# LedController.net
KiCad netlist of a schematic drawn in EAGLE
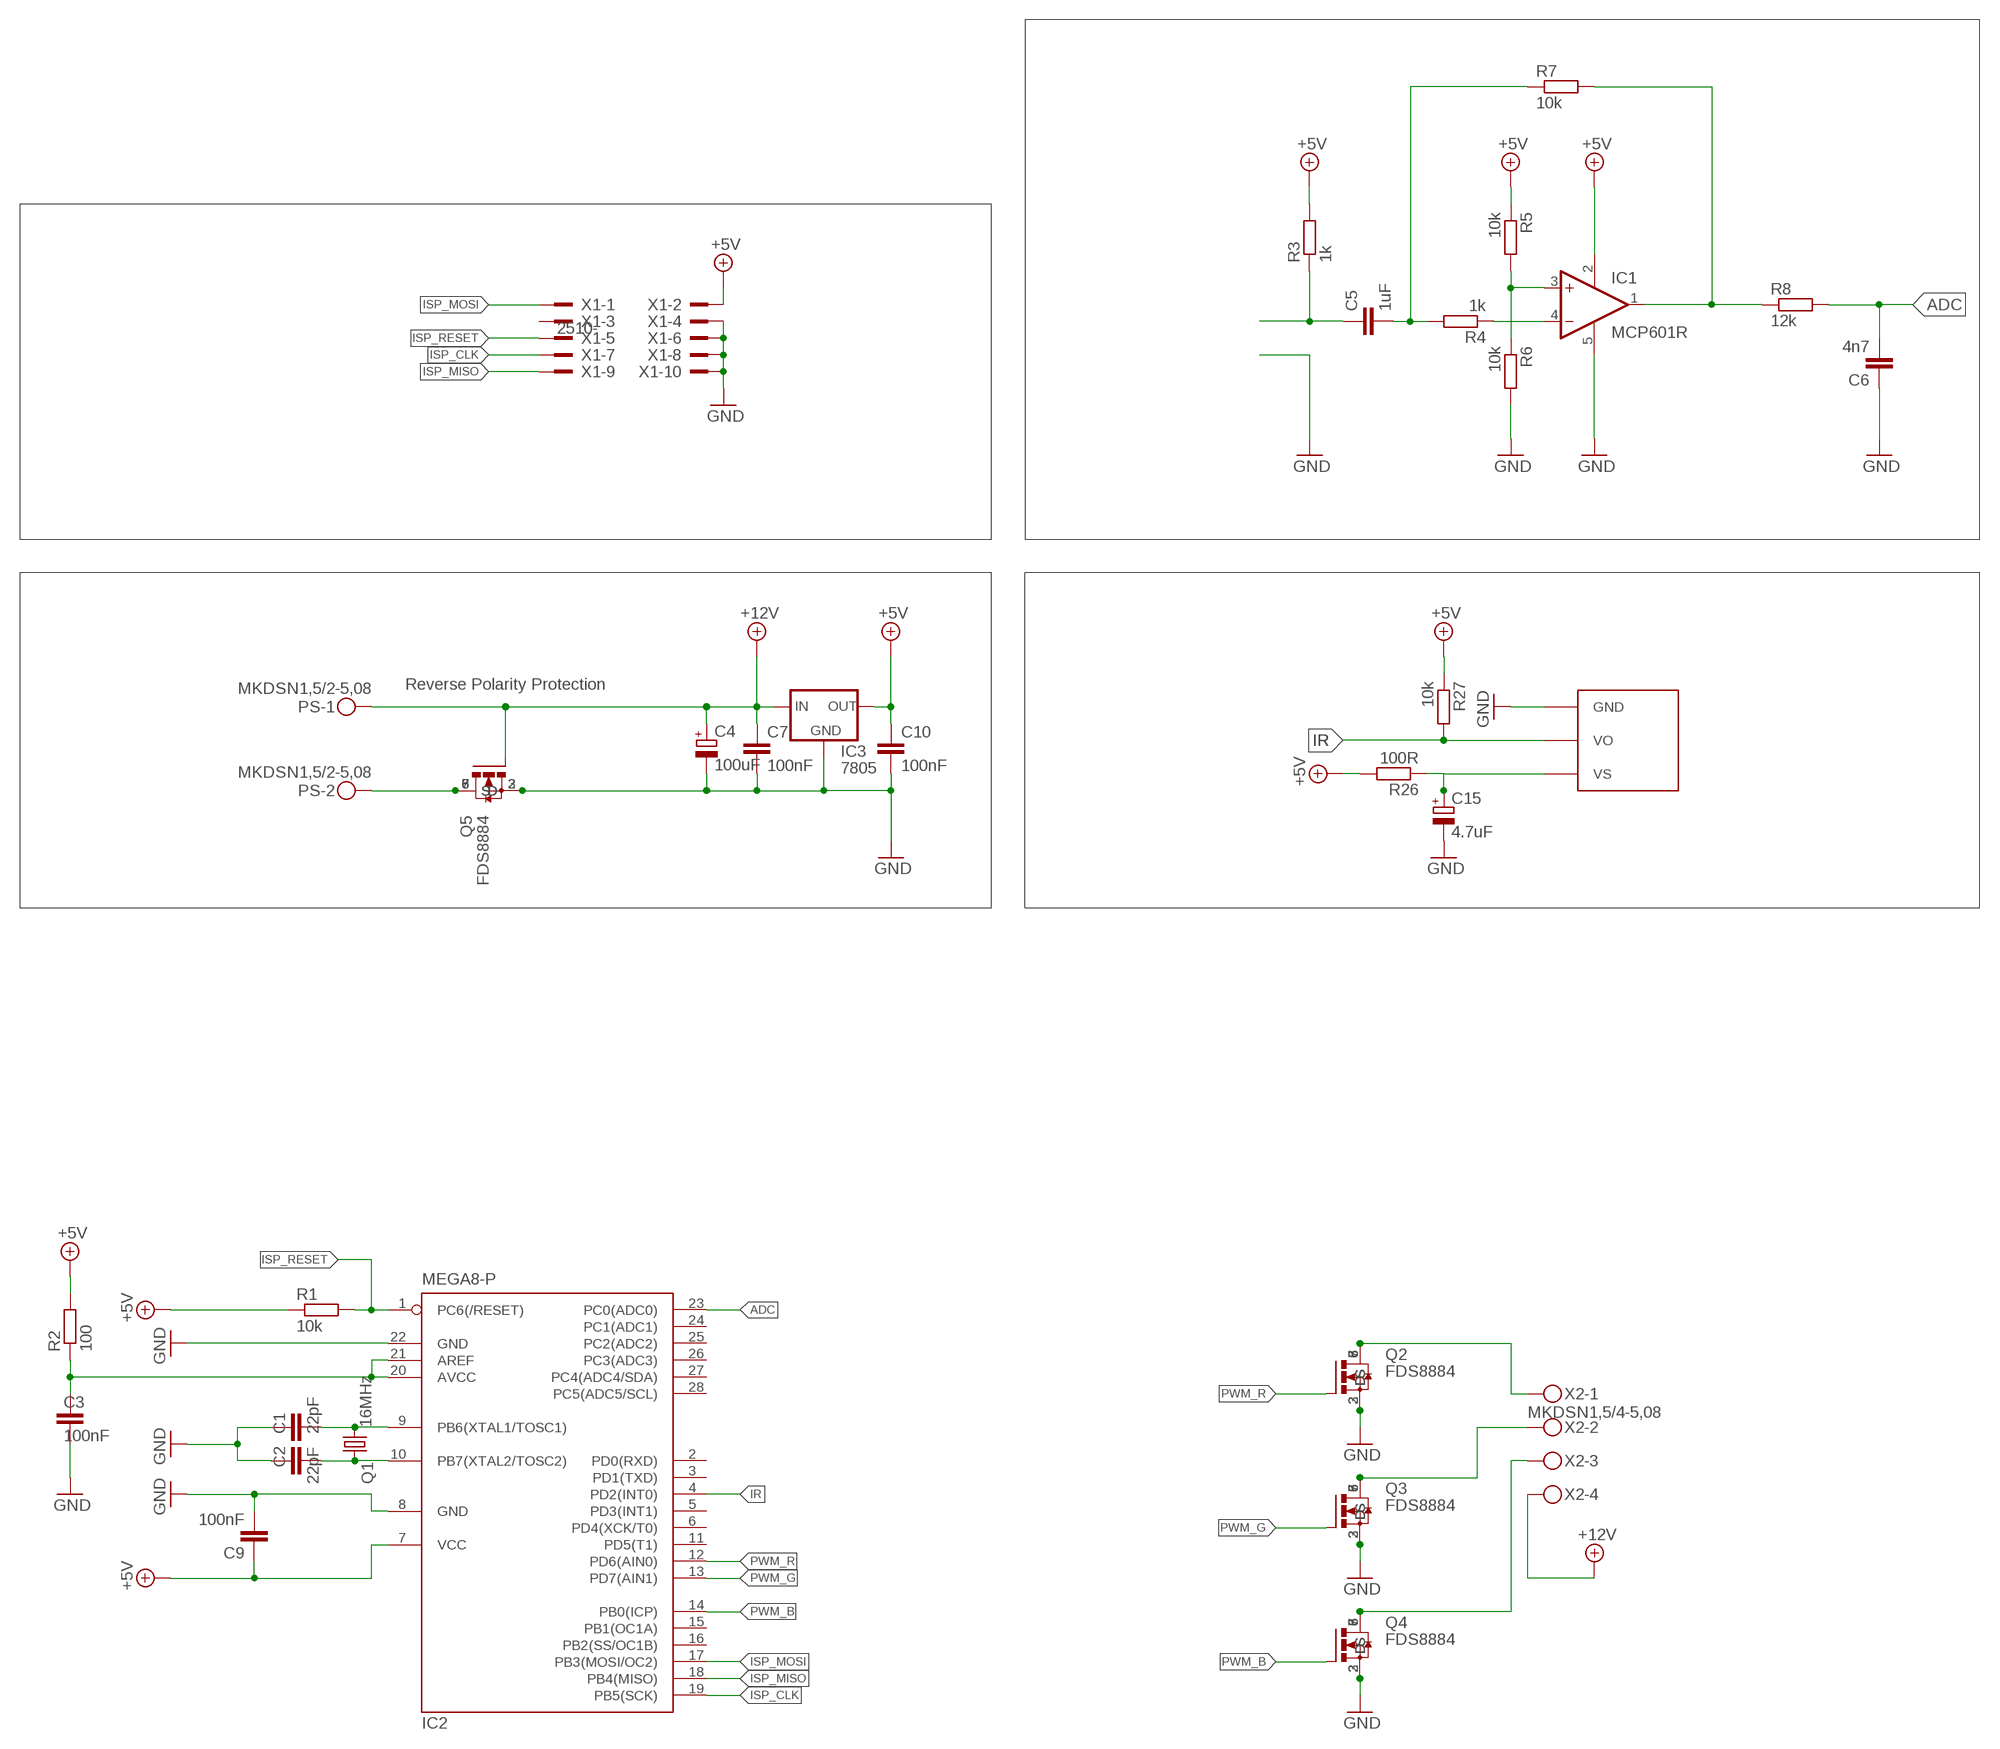
[diagram p0: schematic, sheet 1]

(export (version "E")
  (design (tool "Eeschema 10.0.6"))
  (components
    (comp (ref "C1")
      (value "22pF")
      (footprint "eagle-import:C025-025X050")
      (libsource (lib "eagle-import") (part "C-EU025-025X050"))
    )
    (comp (ref "C2")
      (value "22pF")
      (footprint "eagle-import:C025-025X050")
      (libsource (lib "eagle-import") (part "C-EU025-025X050"))
    )
    (comp (ref "C3")
      (value "100nF")
      (footprint "eagle-import:C025-025X050")
      (libsource (lib "eagle-import") (part "C-EU025-025X050"))
    )
    (comp (ref "C4")
      (value "100uF")
      (footprint "eagle-import:E2-5")
      (libsource (lib "eagle-import") (part "CPOL-EUE2-5"))
    )
    (comp (ref "C5")
      (value "1uF")
      (footprint "eagle-import:C025-024X044")
      (libsource (lib "eagle-import") (part "C-EU025-024X044"))
    )
    (comp (ref "C6")
      (value "4n7")
      (footprint "eagle-import:C025-024X044")
      (libsource (lib "eagle-import") (part "C-EU025-024X044"))
    )
    (comp (ref "C7")
      (value "100nF")
      (footprint "eagle-import:C025-024X044")
      (libsource (lib "eagle-import") (part "C-EU025-024X044"))
    )
    (comp (ref "C9")
      (value "100nF")
      (footprint "eagle-import:C025-024X044")
      (libsource (lib "eagle-import") (part "C-EU025-024X044"))
    )
    (comp (ref "C10")
      (value "100nF")
      (footprint "eagle-import:C025-024X044")
      (libsource (lib "eagle-import") (part "C-EU025-024X044"))
    )
    (comp (ref "C15")
      (value "4.7uF")
      (footprint "eagle-import:E2-5")
      (libsource (lib "eagle-import") (part "CPOL-EUE2-5"))
    )
    (comp (ref "IC1")
      (value "MCP601R")
      (footprint "eagle-import:SOT23-5")
      (libsource (lib "eagle-import") (part "MCP601R"))
    )
    (comp (ref "IC2")
      (value "MEGA8-P")
      (footprint "eagle-import:DIL28-3")
      (libsource (lib "eagle-import") (part "MEGA8-P"))
    )
    (comp (ref "IC3")
      (value "7805")
      (footprint "eagle-import:78XXS")
      (libsource (lib "eagle-import") (part "78XXS"))
    )
    (comp (ref "PS")
      (value "MKDSN1,5/2-5,08")
      (footprint "eagle-import:MKDSN1,5_2-5,08")
      (libsource (lib "eagle-import") (part "MKDSN1,5/2-5,08"))
    )
    (comp (ref "Q1")
      (value "16MHz")
      (footprint "eagle-import:HC49_S")
      (libsource (lib "eagle-import") (part "CRYSTALHC49S"))
    )
    (comp (ref "Q2")
      (value "FDS8884")
      (footprint "eagle-import:SO08")
      (libsource (lib "eagle-import") (part "FDS8884"))
    )
    (comp (ref "Q3")
      (value "FDS8884")
      (footprint "eagle-import:SO08")
      (libsource (lib "eagle-import") (part "FDS8884"))
    )
    (comp (ref "Q4")
      (value "FDS8884")
      (footprint "eagle-import:SO08")
      (libsource (lib "eagle-import") (part "FDS8884"))
    )
    (comp (ref "Q5")
      (value "FDS8884")
      (footprint "eagle-import:SO08")
      (libsource (lib "eagle-import") (part "FDS8884"))
    )
    (comp (ref "R1")
      (value "10k")
      (footprint "eagle-import:0207_2V")
      (libsource (lib "eagle-import") (part "R-EU_0207/2V"))
    )
    (comp (ref "R2")
      (value "100")
      (footprint "eagle-import:0207_2V")
      (libsource (lib "eagle-import") (part "R-EU_0207/2V"))
    )
    (comp (ref "R3")
      (value "1k")
      (footprint "eagle-import:0207_2V")
      (libsource (lib "eagle-import") (part "R-EU_0207/2V"))
    )
    (comp (ref "R4")
      (value "1k")
      (footprint "eagle-import:0207_2V")
      (libsource (lib "eagle-import") (part "R-EU_0207/2V"))
    )
    (comp (ref "R5")
      (value "10k")
      (footprint "eagle-import:0207_2V")
      (libsource (lib "eagle-import") (part "R-EU_0207/2V"))
    )
    (comp (ref "R6")
      (value "10k")
      (footprint "eagle-import:0207_2V")
      (libsource (lib "eagle-import") (part "R-EU_0207/2V"))
    )
    (comp (ref "R7")
      (value "10k")
      (footprint "eagle-import:0207_2V")
      (libsource (lib "eagle-import") (part "R-EU_0207/2V"))
    )
    (comp (ref "R8")
      (value "12k")
      (footprint "eagle-import:0207_2V")
      (libsource (lib "eagle-import") (part "R-EU_0207/2V"))
    )
    (comp (ref "R26")
      (value "100R")
      (footprint "eagle-import:0207_10")
      (libsource (lib "eagle-import") (part "R-EU_0207/10"))
    )
    (comp (ref "R27")
      (value "10k")
      (footprint "eagle-import:0207_10")
      (libsource (lib "eagle-import") (part "R-EU_0207/10"))
    )
    (comp (ref "TSOP")
      (value "TSOP")
      (footprint "eagle-import:TSOP")
      (libsource (lib "eagle-import") (part "TSOP"))
    )
    (comp (ref "X1")
      (value "2510-")
      (footprint "eagle-import:PAK100_2500-10")
      (libsource (lib "eagle-import") (part "2510-"))
    )
    (comp (ref "X2")
      (value "MKDSN1,5/4-5,08")
      (footprint "eagle-import:MKDSN1,5_4-5,08")
      (libsource (lib "eagle-import") (part "MKDSN1,5/4-5,08"))
    )
  )
  (nets
    (net (code "1") (name "+5V") (class "Default")
      (node (ref "C10") (pin "1") (pinfunction "1_1") (pintype "passive"))
      (node (ref "C9") (pin "1") (pinfunction "1_1") (pintype "passive"))
      (node (ref "IC1") (pin "2") (pinfunction "V+_2") (pintype "power_in"))
      (node (ref "IC2") (pin "7") (pinfunction "VCC_7") (pintype "power_in"))
      (node (ref "IC3") (pin "OUT") (pinfunction "OUT_OUT") (pintype "passive"))
      (node (ref "R1") (pin "1") (pinfunction "1_1") (pintype "passive"))
      (node (ref "R2") (pin "2") (pinfunction "2_2") (pintype "passive"))
      (node (ref "R26") (pin "2") (pinfunction "2_2") (pintype "passive"))
      (node (ref "R27") (pin "1") (pinfunction "1_1") (pintype "passive"))
      (node (ref "R3") (pin "2") (pinfunction "2_2") (pintype "passive"))
      (node (ref "R5") (pin "1") (pinfunction "1_1") (pintype "passive"))
      (node (ref "X1") (pin "2") (pinfunction "KL_2") (pintype "passive"))
    )
    (net (code "2") (name "+12V") (class "Default")
      (node (ref "C4") (pin "+") (pinfunction "+_+") (pintype "passive"))
      (node (ref "C7") (pin "1") (pinfunction "1_1") (pintype "passive"))
      (node (ref "IC3") (pin "IN") (pinfunction "IN_IN") (pintype "input"))
      (node (ref "PS") (pin "1") (pinfunction "KL_1") (pintype "passive"))
      (node (ref "Q5") (pin "4") (pinfunction "G_4") (pintype "passive"))
      (node (ref "X2") (pin "4") (pinfunction "KL_4") (pintype "passive"))
    )
    (net (code "3") (name "ADC") (class "Default")
      (node (ref "C6") (pin "2") (pinfunction "2_2") (pintype "passive"))
      (node (ref "IC2") (pin "23") (pinfunction "PC0(ADC0)_23") (pintype "bidirectional"))
      (node (ref "R8") (pin "2") (pinfunction "2_2") (pintype "passive"))
    )
    (net (code "4") (name "GND") (class "Default")
      (node (ref "C1") (pin "1") (pinfunction "1_1") (pintype "passive"))
      (node (ref "C10") (pin "2") (pinfunction "2_2") (pintype "passive"))
      (node (ref "C15") (pin "-") (pinfunction "-_-") (pintype "passive"))
      (node (ref "C2") (pin "1") (pinfunction "1_1") (pintype "passive"))
      (node (ref "C3") (pin "2") (pinfunction "2_2") (pintype "passive"))
      (node (ref "C4") (pin "-") (pinfunction "-_-") (pintype "passive"))
      (node (ref "C6") (pin "1") (pinfunction "1_1") (pintype "passive"))
      (node (ref "C7") (pin "2") (pinfunction "2_2") (pintype "passive"))
      (node (ref "C9") (pin "2") (pinfunction "2_2") (pintype "passive"))
      (node (ref "IC1") (pin "5") (pinfunction "V-_5") (pintype "power_in"))
      (node (ref "IC2") (pin "22") (pinfunction "GND_22") (pintype "power_in"))
      (node (ref "IC2") (pin "8") (pinfunction "GND_8") (pintype "power_in"))
      (node (ref "IC3") (pin "GND") (pinfunction "GND_GND") (pintype "input"))
      (node (ref "Q2") (pin "1") (pinfunction "S_1") (pintype "passive"))
      (node (ref "Q2") (pin "2") (pinfunction "S_2") (pintype "bidirectional"))
      (node (ref "Q2") (pin "3") (pinfunction "S_3") (pintype "bidirectional"))
      (node (ref "Q3") (pin "1") (pinfunction "S_1") (pintype "passive"))
      (node (ref "Q3") (pin "2") (pinfunction "S_2") (pintype "bidirectional"))
      (node (ref "Q3") (pin "3") (pinfunction "S_3") (pintype "bidirectional"))
      (node (ref "Q4") (pin "1") (pinfunction "S_1") (pintype "passive"))
      (node (ref "Q4") (pin "2") (pinfunction "S_2") (pintype "bidirectional"))
      (node (ref "Q4") (pin "3") (pinfunction "S_3") (pintype "bidirectional"))
      (node (ref "Q5") (pin "1") (pinfunction "S_1") (pintype "passive"))
      (node (ref "Q5") (pin "2") (pinfunction "S_2") (pintype "bidirectional"))
      (node (ref "Q5") (pin "3") (pinfunction "S_3") (pintype "bidirectional"))
      (node (ref "R6") (pin "2") (pinfunction "2_2") (pintype "passive"))
      (node (ref "TSOP") (pin "GND") (pinfunction "GND_GND") (pintype "bidirectional"))
      (node (ref "X1") (pin "10") (pinfunction "KL_10") (pintype "passive"))
      (node (ref "X1") (pin "4") (pinfunction "KL_4") (pintype "passive"))
      (node (ref "X1") (pin "6") (pinfunction "KL_6") (pintype "passive"))
      (node (ref "X1") (pin "8") (pinfunction "KL_8") (pintype "passive"))
    )
    (net (code "5") (name "IR") (class "Default")
      (node (ref "IC2") (pin "4") (pinfunction "PD2(INT0)_4") (pintype "bidirectional"))
      (node (ref "R27") (pin "2") (pinfunction "2_2") (pintype "passive"))
      (node (ref "TSOP") (pin "VO") (pinfunction "VO_VO") (pintype "bidirectional"))
    )
    (net (code "6") (name "ISP_CLK") (class "Default")
      (node (ref "IC2") (pin "19") (pinfunction "PB5(SCK)_19") (pintype "bidirectional"))
      (node (ref "X1") (pin "7") (pinfunction "KL_7") (pintype "passive"))
    )
    (net (code "7") (name "ISP_MISO") (class "Default")
      (node (ref "IC2") (pin "18") (pinfunction "PB4(MISO)_18") (pintype "bidirectional"))
      (node (ref "X1") (pin "9") (pinfunction "KL_9") (pintype "passive"))
    )
    (net (code "8") (name "ISP_MOSI") (class "Default")
      (node (ref "IC2") (pin "17") (pinfunction "PB3(MOSI/OC2)_17") (pintype "bidirectional"))
      (node (ref "X1") (pin "1") (pinfunction "KL_1") (pintype "passive"))
    )
    (net (code "9") (name "ISP_RESET") (class "Default")
      (node (ref "IC2") (pin "1") (pinfunction "PC6(/RESET)_1") (pintype "bidirectional"))
      (node (ref "R1") (pin "2") (pinfunction "2_2") (pintype "passive"))
      (node (ref "X1") (pin "5") (pinfunction "KL_5") (pintype "passive"))
    )
    (net (code "10") (name "Net-(C5-Pad1)") (class "Default")
      (node (ref "C5") (pin "1") (pinfunction "1_1") (pintype "passive"))
      (node (ref "R3") (pin "1") (pinfunction "1_1") (pintype "passive"))
    )
    (net (code "11") (name "Net-(C5-Pad2)") (class "Default")
      (node (ref "C5") (pin "2") (pinfunction "2_2") (pintype "passive"))
      (node (ref "R4") (pin "2") (pinfunction "2_2") (pintype "passive"))
      (node (ref "R7") (pin "1") (pinfunction "1_1") (pintype "passive"))
    )
    (net (code "12") (name "Net-(C15-Pad+)") (class "Default")
      (node (ref "C15") (pin "+") (pinfunction "+_+") (pintype "passive"))
      (node (ref "R26") (pin "1") (pinfunction "1_1") (pintype "passive"))
      (node (ref "TSOP") (pin "VS") (pinfunction "VS_VS") (pintype "bidirectional"))
    )
    (net (code "13") (name "Net-(IC1-+IN)") (class "Default")
      (node (ref "IC1") (pin "3") (pinfunction "+IN_3") (pintype "input"))
      (node (ref "R5") (pin "2") (pinfunction "2_2") (pintype "passive"))
      (node (ref "R6") (pin "1") (pinfunction "1_1") (pintype "passive"))
    )
    (net (code "14") (name "Net-(IC1--IN)") (class "Default")
      (node (ref "IC1") (pin "4") (pinfunction "-IN_4") (pintype "input"))
      (node (ref "R4") (pin "1") (pinfunction "1_1") (pintype "passive"))
    )
    (net (code "15") (name "Net-(IC1-OUT)") (class "Default")
      (node (ref "IC1") (pin "1") (pinfunction "OUT_1") (pintype "output"))
      (node (ref "R7") (pin "2") (pinfunction "2_2") (pintype "passive"))
      (node (ref "R8") (pin "1") (pinfunction "1_1") (pintype "passive"))
    )
    (net (code "16") (name "Net-(IC2-AREF)") (class "Default")
      (node (ref "C3") (pin "1") (pinfunction "1_1") (pintype "passive"))
      (node (ref "IC2") (pin "20") (pinfunction "AVCC_20") (pintype "power_in"))
      (node (ref "IC2") (pin "21") (pinfunction "AREF_21") (pintype "passive"))
      (node (ref "R2") (pin "1") (pinfunction "1_1") (pintype "passive"))
    )
    (net (code "17") (name "Net-(IC2-PB6(XTAL1{slash}TOSC1))") (class "Default")
      (node (ref "C1") (pin "2") (pinfunction "2_2") (pintype "passive"))
      (node (ref "IC2") (pin "9") (pinfunction "PB6(XTAL1/TOSC1)_9") (pintype "bidirectional"))
      (node (ref "Q1") (pin "2") (pinfunction "2_2") (pintype "passive"))
    )
    (net (code "18") (name "Net-(IC2-PB7(XTAL2{slash}TOSC2))") (class "Default")
      (node (ref "C2") (pin "2") (pinfunction "2_2") (pintype "passive"))
      (node (ref "IC2") (pin "10") (pinfunction "PB7(XTAL2/TOSC2)_10") (pintype "bidirectional"))
      (node (ref "Q1") (pin "1") (pinfunction "1_1") (pintype "passive"))
    )
    (net (code "19") (name "Net-(PSB-KL)") (class "Default")
      (node (ref "PS") (pin "2") (pinfunction "KL_2") (pintype "passive"))
      (node (ref "Q5") (pin "5") (pinfunction "D_5") (pintype "passive"))
      (node (ref "Q5") (pin "6") (pinfunction "D_6") (pintype "bidirectional"))
      (node (ref "Q5") (pin "7") (pinfunction "D_7") (pintype "bidirectional"))
      (node (ref "Q5") (pin "8") (pinfunction "D_8") (pintype "bidirectional"))
    )
    (net (code "20") (name "Net-(X2A-KL)") (class "Default")
      (node (ref "Q2") (pin "5") (pinfunction "D_5") (pintype "passive"))
      (node (ref "Q2") (pin "6") (pinfunction "D_6") (pintype "bidirectional"))
      (node (ref "Q2") (pin "7") (pinfunction "D_7") (pintype "bidirectional"))
      (node (ref "Q2") (pin "8") (pinfunction "D_8") (pintype "bidirectional"))
      (node (ref "X2") (pin "1") (pinfunction "KL_1") (pintype "passive"))
    )
    (net (code "21") (name "Net-(X2B-KL)") (class "Default")
      (node (ref "Q3") (pin "5") (pinfunction "D_5") (pintype "passive"))
      (node (ref "Q3") (pin "6") (pinfunction "D_6") (pintype "bidirectional"))
      (node (ref "Q3") (pin "7") (pinfunction "D_7") (pintype "bidirectional"))
      (node (ref "Q3") (pin "8") (pinfunction "D_8") (pintype "bidirectional"))
      (node (ref "X2") (pin "2") (pinfunction "KL_2") (pintype "passive"))
    )
    (net (code "22") (name "Net-(X2C-KL)") (class "Default")
      (node (ref "Q4") (pin "5") (pinfunction "D_5") (pintype "passive"))
      (node (ref "Q4") (pin "6") (pinfunction "D_6") (pintype "bidirectional"))
      (node (ref "Q4") (pin "7") (pinfunction "D_7") (pintype "bidirectional"))
      (node (ref "Q4") (pin "8") (pinfunction "D_8") (pintype "bidirectional"))
      (node (ref "X2") (pin "3") (pinfunction "KL_3") (pintype "passive"))
    )
    (net (code "23") (name "PWM_B") (class "Default")
      (node (ref "IC2") (pin "14") (pinfunction "PB0(ICP)_14") (pintype "bidirectional"))
      (node (ref "Q4") (pin "4") (pinfunction "G_4") (pintype "passive"))
    )
    (net (code "24") (name "PWM_G") (class "Default")
      (node (ref "IC2") (pin "13") (pinfunction "PD7(AIN1)_13") (pintype "bidirectional"))
      (node (ref "Q3") (pin "4") (pinfunction "G_4") (pintype "passive"))
    )
    (net (code "25") (name "PWM_R") (class "Default")
      (node (ref "IC2") (pin "12") (pinfunction "PD6(AIN0)_12") (pintype "bidirectional"))
      (node (ref "Q2") (pin "4") (pinfunction "G_4") (pintype "passive"))
    )
    (net (code "26") (name "unconnected-(IC2-PB1(OC1A)-Pad15)") (class "Default")
      (node (ref "IC2") (pin "15") (pinfunction "PB1(OC1A)_15") (pintype "bidirectional"))
    )
    (net (code "27") (name "unconnected-(IC2-PB2(SS{slash}OC1B)-Pad16)") (class "Default")
      (node (ref "IC2") (pin "16") (pinfunction "PB2(SS/OC1B)_16") (pintype "bidirectional"))
    )
    (net (code "28") (name "unconnected-(IC2-PC1(ADC1)-Pad24)") (class "Default")
      (node (ref "IC2") (pin "24") (pinfunction "PC1(ADC1)_24") (pintype "bidirectional"))
    )
    (net (code "29") (name "unconnected-(IC2-PC2(ADC2)-Pad25)") (class "Default")
      (node (ref "IC2") (pin "25") (pinfunction "PC2(ADC2)_25") (pintype "bidirectional"))
    )
    (net (code "30") (name "unconnected-(IC2-PC3(ADC3)-Pad26)") (class "Default")
      (node (ref "IC2") (pin "26") (pinfunction "PC3(ADC3)_26") (pintype "bidirectional"))
    )
    (net (code "31") (name "unconnected-(IC2-PC4(ADC4{slash}SDA)-Pad27)") (class "Default")
      (node (ref "IC2") (pin "27") (pinfunction "PC4(ADC4/SDA)_27") (pintype "bidirectional"))
    )
    (net (code "32") (name "unconnected-(IC2-PC5(ADC5{slash}SCL)-Pad28)") (class "Default")
      (node (ref "IC2") (pin "28") (pinfunction "PC5(ADC5/SCL)_28") (pintype "bidirectional"))
    )
    (net (code "33") (name "unconnected-(IC2-PD0(RXD)-Pad2)") (class "Default")
      (node (ref "IC2") (pin "2") (pinfunction "PD0(RXD)_2") (pintype "bidirectional"))
    )
    (net (code "34") (name "unconnected-(IC2-PD1(TXD)-Pad3)") (class "Default")
      (node (ref "IC2") (pin "3") (pinfunction "PD1(TXD)_3") (pintype "bidirectional"))
    )
    (net (code "35") (name "unconnected-(IC2-PD3(INT1)-Pad5)") (class "Default")
      (node (ref "IC2") (pin "5") (pinfunction "PD3(INT1)_5") (pintype "bidirectional"))
    )
    (net (code "36") (name "unconnected-(IC2-PD4(XCK{slash}T0)-Pad6)") (class "Default")
      (node (ref "IC2") (pin "6") (pinfunction "PD4(XCK/T0)_6") (pintype "bidirectional"))
    )
    (net (code "37") (name "unconnected-(IC2-PD5(T1)-Pad11)") (class "Default")
      (node (ref "IC2") (pin "11") (pinfunction "PD5(T1)_11") (pintype "bidirectional"))
    )
    (net (code "38") (name "unconnected-(X1D-KL-Pad3)") (class "Default")
      (node (ref "X1") (pin "3") (pinfunction "KL_3") (pintype "passive"))
    )
  )
)
